# Edge_Slot_Interface.net
KiCad netlist of a schematic drawn in Altium Designer
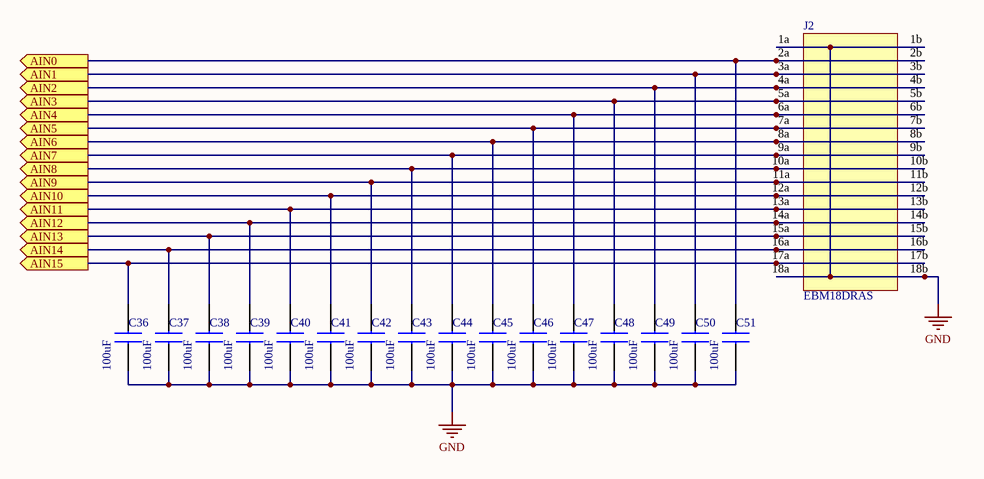
[diagram p0: Edge_Slot_Interface.SchDoc]

(export (version "E")
  (design (tool "Eeschema 10.0.6"))
  (components
    (comp (ref "C36")
      (value "100uF")
      (footprint "Cap_0805")
      (description "Multilayer Ceramic Capacitors MLCC - SMD/SMT 10uF 25volts 10%")
      (fields
        (field (name "MANUFACTURER_PART_NUMBER") "VJ1206G106KXXTW1BC")
        (field (name "MOUSER PART NUMBER") "77-VJ126G106KXXTW1BC")
      )
      (libsource (lib "10uF_1206") (part "VJ1206G106KXXTW1BC"))
    )
    (comp (ref "C37")
      (value "100uF")
      (footprint "Cap_0805")
      (description "Multilayer Ceramic Capacitors MLCC - SMD/SMT 10uF 25volts 10%")
      (fields
        (field (name "MANUFACTURER_PART_NUMBER") "VJ1206G106KXXTW1BC")
        (field (name "MOUSER PART NUMBER") "77-VJ126G106KXXTW1BC")
      )
      (libsource (lib "10uF_1206") (part "VJ1206G106KXXTW1BC"))
    )
    (comp (ref "C38")
      (value "100uF")
      (footprint "Cap_0805")
      (description "Multilayer Ceramic Capacitors MLCC - SMD/SMT 10uF 25volts 10%")
      (fields
        (field (name "MANUFACTURER_PART_NUMBER") "VJ1206G106KXXTW1BC")
        (field (name "MOUSER PART NUMBER") "77-VJ126G106KXXTW1BC")
      )
      (libsource (lib "10uF_1206") (part "VJ1206G106KXXTW1BC"))
    )
    (comp (ref "C39")
      (value "100uF")
      (footprint "Cap_0805")
      (description "Multilayer Ceramic Capacitors MLCC - SMD/SMT 10uF 25volts 10%")
      (fields
        (field (name "MANUFACTURER_PART_NUMBER") "VJ1206G106KXXTW1BC")
        (field (name "MOUSER PART NUMBER") "77-VJ126G106KXXTW1BC")
      )
      (libsource (lib "10uF_1206") (part "VJ1206G106KXXTW1BC"))
    )
    (comp (ref "C40")
      (value "100uF")
      (footprint "Cap_0805")
      (description "Multilayer Ceramic Capacitors MLCC - SMD/SMT 10uF 25volts 10%")
      (fields
        (field (name "MANUFACTURER_PART_NUMBER") "VJ1206G106KXXTW1BC")
        (field (name "MOUSER PART NUMBER") "77-VJ126G106KXXTW1BC")
      )
      (libsource (lib "10uF_1206") (part "VJ1206G106KXXTW1BC"))
    )
    (comp (ref "C41")
      (value "100uF")
      (footprint "Cap_0805")
      (description "Multilayer Ceramic Capacitors MLCC - SMD/SMT 10uF 25volts 10%")
      (fields
        (field (name "MANUFACTURER_PART_NUMBER") "VJ1206G106KXXTW1BC")
        (field (name "MOUSER PART NUMBER") "77-VJ126G106KXXTW1BC")
      )
      (libsource (lib "10uF_1206") (part "VJ1206G106KXXTW1BC"))
    )
    (comp (ref "C42")
      (value "100uF")
      (footprint "Cap_0805")
      (description "Multilayer Ceramic Capacitors MLCC - SMD/SMT 10uF 25volts 10%")
      (fields
        (field (name "MANUFACTURER_PART_NUMBER") "VJ1206G106KXXTW1BC")
        (field (name "MOUSER PART NUMBER") "77-VJ126G106KXXTW1BC")
      )
      (libsource (lib "10uF_1206") (part "VJ1206G106KXXTW1BC"))
    )
    (comp (ref "C43")
      (value "100uF")
      (footprint "Cap_0805")
      (description "Multilayer Ceramic Capacitors MLCC - SMD/SMT 10uF 25volts 10%")
      (fields
        (field (name "MANUFACTURER_PART_NUMBER") "VJ1206G106KXXTW1BC")
        (field (name "MOUSER PART NUMBER") "77-VJ126G106KXXTW1BC")
      )
      (libsource (lib "10uF_1206") (part "VJ1206G106KXXTW1BC"))
    )
    (comp (ref "C44")
      (value "100uF")
      (footprint "Cap_0805")
      (description "Multilayer Ceramic Capacitors MLCC - SMD/SMT 10uF 25volts 10%")
      (fields
        (field (name "MANUFACTURER_PART_NUMBER") "VJ1206G106KXXTW1BC")
        (field (name "MOUSER PART NUMBER") "77-VJ126G106KXXTW1BC")
      )
      (libsource (lib "10uF_1206") (part "VJ1206G106KXXTW1BC"))
    )
    (comp (ref "C45")
      (value "100uF")
      (footprint "Cap_0805")
      (description "Multilayer Ceramic Capacitors MLCC - SMD/SMT 10uF 25volts 10%")
      (fields
        (field (name "MANUFACTURER_PART_NUMBER") "VJ1206G106KXXTW1BC")
        (field (name "MOUSER PART NUMBER") "77-VJ126G106KXXTW1BC")
      )
      (libsource (lib "10uF_1206") (part "VJ1206G106KXXTW1BC"))
    )
    (comp (ref "C46")
      (value "100uF")
      (footprint "Cap_0805")
      (description "Multilayer Ceramic Capacitors MLCC - SMD/SMT 10uF 25volts 10%")
      (fields
        (field (name "MANUFACTURER_PART_NUMBER") "VJ1206G106KXXTW1BC")
        (field (name "MOUSER PART NUMBER") "77-VJ126G106KXXTW1BC")
      )
      (libsource (lib "10uF_1206") (part "VJ1206G106KXXTW1BC"))
    )
    (comp (ref "C47")
      (value "100uF")
      (footprint "Cap_0805")
      (description "Multilayer Ceramic Capacitors MLCC - SMD/SMT 10uF 25volts 10%")
      (fields
        (field (name "MANUFACTURER_PART_NUMBER") "VJ1206G106KXXTW1BC")
        (field (name "MOUSER PART NUMBER") "77-VJ126G106KXXTW1BC")
      )
      (libsource (lib "10uF_1206") (part "VJ1206G106KXXTW1BC"))
    )
    (comp (ref "C48")
      (value "100uF")
      (footprint "Cap_0805")
      (description "Multilayer Ceramic Capacitors MLCC - SMD/SMT 10uF 25volts 10%")
      (fields
        (field (name "MANUFACTURER_PART_NUMBER") "VJ1206G106KXXTW1BC")
        (field (name "MOUSER PART NUMBER") "77-VJ126G106KXXTW1BC")
      )
      (libsource (lib "10uF_1206") (part "VJ1206G106KXXTW1BC"))
    )
    (comp (ref "C49")
      (value "100uF")
      (footprint "Cap_0805")
      (description "Multilayer Ceramic Capacitors MLCC - SMD/SMT 10uF 25volts 10%")
      (fields
        (field (name "MANUFACTURER_PART_NUMBER") "VJ1206G106KXXTW1BC")
        (field (name "MOUSER PART NUMBER") "77-VJ126G106KXXTW1BC")
      )
      (libsource (lib "10uF_1206") (part "VJ1206G106KXXTW1BC"))
    )
    (comp (ref "C50")
      (value "100uF")
      (footprint "Cap_0805")
      (description "Multilayer Ceramic Capacitors MLCC - SMD/SMT 10uF 25volts 10%")
      (fields
        (field (name "MANUFACTURER_PART_NUMBER") "VJ1206G106KXXTW1BC")
        (field (name "MOUSER PART NUMBER") "77-VJ126G106KXXTW1BC")
      )
      (libsource (lib "10uF_1206") (part "VJ1206G106KXXTW1BC"))
    )
    (comp (ref "C51")
      (value "100uF")
      (footprint "Cap_0805")
      (description "Multilayer Ceramic Capacitors MLCC - SMD/SMT 10uF 25volts 10%")
      (fields
        (field (name "MANUFACTURER_PART_NUMBER") "VJ1206G106KXXTW1BC")
        (field (name "MOUSER PART NUMBER") "77-VJ126G106KXXTW1BC")
      )
      (libsource (lib "10uF_1206") (part "VJ1206G106KXXTW1BC"))
    )
    (comp (ref "J2")
      (value "EBM18DRAS")
      (footprint "EBM18DRAS")
      (description "CONN EDGE DUAL FMALE 18POS 0.051mm dia")
      (libsource (lib "CV-R-BAP_V2.1.5") (part "EBM18DRAS"))
    )
  )
  (nets
    (net (code "1") (name "/AIN0") (class "Default")
      (node (ref "C51") (pin "2") (pinfunction "2_2") (pintype "passive"))
      (node (ref "J2") (pin "2a") (pinfunction "2a_2a") (pintype "passive"))
      (node (ref "J2") (pin "2b") (pinfunction "2b_2b") (pintype "passive"))
    )
    (net (code "2") (name "/AIN1") (class "Default")
      (node (ref "C50") (pin "2") (pinfunction "2_2") (pintype "passive"))
      (node (ref "J2") (pin "3a") (pinfunction "3a_3a") (pintype "passive"))
      (node (ref "J2") (pin "3b") (pinfunction "3b_3b") (pintype "passive"))
    )
    (net (code "3") (name "/AIN2") (class "Default")
      (node (ref "C49") (pin "2") (pinfunction "2_2") (pintype "passive"))
      (node (ref "J2") (pin "4a") (pinfunction "4a_4a") (pintype "passive"))
      (node (ref "J2") (pin "4b") (pinfunction "4b_4b") (pintype "passive"))
    )
    (net (code "4") (name "/AIN3") (class "Default")
      (node (ref "C48") (pin "2") (pinfunction "2_2") (pintype "passive"))
      (node (ref "J2") (pin "5a") (pinfunction "8_5a") (pintype "passive"))
      (node (ref "J2") (pin "5b") (pinfunction "5b_5b") (pintype "passive"))
    )
    (net (code "5") (name "/AIN4") (class "Default")
      (node (ref "C47") (pin "2") (pinfunction "2_2") (pintype "passive"))
      (node (ref "J2") (pin "6a") (pinfunction "6a_6a") (pintype "passive"))
      (node (ref "J2") (pin "6b") (pinfunction "6b_6b") (pintype "passive"))
    )
    (net (code "6") (name "/AIN5") (class "Default")
      (node (ref "C46") (pin "2") (pinfunction "2_2") (pintype "passive"))
      (node (ref "J2") (pin "7a") (pinfunction "7a_7a") (pintype "passive"))
      (node (ref "J2") (pin "7b") (pinfunction "7b_7b") (pintype "passive"))
    )
    (net (code "7") (name "/AIN6") (class "Default")
      (node (ref "C45") (pin "2") (pinfunction "2_2") (pintype "passive"))
      (node (ref "J2") (pin "8a") (pinfunction "14_8a") (pintype "passive"))
      (node (ref "J2") (pin "8b") (pinfunction "8b_8b") (pintype "passive"))
    )
    (net (code "8") (name "/AIN7") (class "Default")
      (node (ref "C44") (pin "2") (pinfunction "2_2") (pintype "passive"))
      (node (ref "J2") (pin "9a") (pinfunction "9a_9a") (pintype "passive"))
      (node (ref "J2") (pin "9b") (pinfunction "9b_9b") (pintype "passive"))
    )
    (net (code "9") (name "/AIN8") (class "Default")
      (node (ref "C43") (pin "2") (pinfunction "2_2") (pintype "passive"))
      (node (ref "J2") (pin "10a") (pinfunction "10a_10a") (pintype "passive"))
      (node (ref "J2") (pin "10b") (pinfunction "10b_10b") (pintype "passive"))
    )
    (net (code "10") (name "/AIN9") (class "Default")
      (node (ref "C42") (pin "2") (pinfunction "2_2") (pintype "passive"))
      (node (ref "J2") (pin "11a") (pinfunction "20_11a") (pintype "passive"))
      (node (ref "J2") (pin "11b") (pinfunction "11b_11b") (pintype "passive"))
    )
    (net (code "11") (name "/AIN10") (class "Default")
      (node (ref "C41") (pin "2") (pinfunction "2_2") (pintype "passive"))
      (node (ref "J2") (pin "12a") (pinfunction "12a_12a") (pintype "passive"))
      (node (ref "J2") (pin "12b") (pinfunction "12b_12b") (pintype "passive"))
    )
    (net (code "12") (name "/AIN11") (class "Default")
      (node (ref "C40") (pin "2") (pinfunction "2_2") (pintype "passive"))
      (node (ref "J2") (pin "13a") (pinfunction "13a_13a") (pintype "passive"))
      (node (ref "J2") (pin "13b") (pinfunction "13b_13b") (pintype "passive"))
    )
    (net (code "13") (name "/AIN12") (class "Default")
      (node (ref "C39") (pin "2") (pinfunction "2_2") (pintype "passive"))
      (node (ref "J2") (pin "14a") (pinfunction "14a_14a") (pintype "passive"))
      (node (ref "J2") (pin "14b") (pinfunction "14b_14b") (pintype "passive"))
    )
    (net (code "14") (name "/AIN13") (class "Default")
      (node (ref "C38") (pin "2") (pinfunction "2_2") (pintype "passive"))
      (node (ref "J2") (pin "15a") (pinfunction "15a_15a") (pintype "passive"))
      (node (ref "J2") (pin "15b") (pinfunction "15b_15b") (pintype "passive"))
    )
    (net (code "15") (name "/AIN14") (class "Default")
      (node (ref "C37") (pin "2") (pinfunction "2_2") (pintype "passive"))
      (node (ref "J2") (pin "16a") (pinfunction "16a_16a") (pintype "passive"))
      (node (ref "J2") (pin "16b") (pinfunction "16b_16b") (pintype "passive"))
    )
    (net (code "16") (name "/AIN15") (class "Default")
      (node (ref "C36") (pin "2") (pinfunction "2_2") (pintype "passive"))
      (node (ref "J2") (pin "17a") (pinfunction "17a_17a") (pintype "passive"))
      (node (ref "J2") (pin "17b") (pinfunction "17b_17b") (pintype "passive"))
    )
    (net (code "17") (name "GND") (class "Default")
      (node (ref "C36") (pin "1") (pinfunction "1_1") (pintype "passive"))
      (node (ref "C37") (pin "1") (pinfunction "1_1") (pintype "passive"))
      (node (ref "C38") (pin "1") (pinfunction "1_1") (pintype "passive"))
      (node (ref "C39") (pin "1") (pinfunction "1_1") (pintype "passive"))
      (node (ref "C40") (pin "1") (pinfunction "1_1") (pintype "passive"))
      (node (ref "C41") (pin "1") (pinfunction "1_1") (pintype "passive"))
      (node (ref "C42") (pin "1") (pinfunction "1_1") (pintype "passive"))
      (node (ref "C43") (pin "1") (pinfunction "1_1") (pintype "passive"))
      (node (ref "C44") (pin "1") (pinfunction "1_1") (pintype "passive"))
      (node (ref "C45") (pin "1") (pinfunction "1_1") (pintype "passive"))
      (node (ref "C46") (pin "1") (pinfunction "1_1") (pintype "passive"))
      (node (ref "C47") (pin "1") (pinfunction "1_1") (pintype "passive"))
      (node (ref "C48") (pin "1") (pinfunction "1_1") (pintype "passive"))
      (node (ref "C49") (pin "1") (pinfunction "1_1") (pintype "passive"))
      (node (ref "C50") (pin "1") (pinfunction "1_1") (pintype "passive"))
      (node (ref "C51") (pin "1") (pinfunction "1_1") (pintype "passive"))
      (node (ref "J2") (pin "18a") (pinfunction "18a_18a") (pintype "passive"))
      (node (ref "J2") (pin "18b") (pinfunction "18b_18b") (pintype "passive"))
      (node (ref "J2") (pin "1a") (pinfunction "1a_1a") (pintype "passive"))
      (node (ref "J2") (pin "1b") (pinfunction "1b_1b") (pintype "passive"))
    )
  )
)
